# 4_motor.net
KiCad netlist of a schematic drawn in Altium Designer
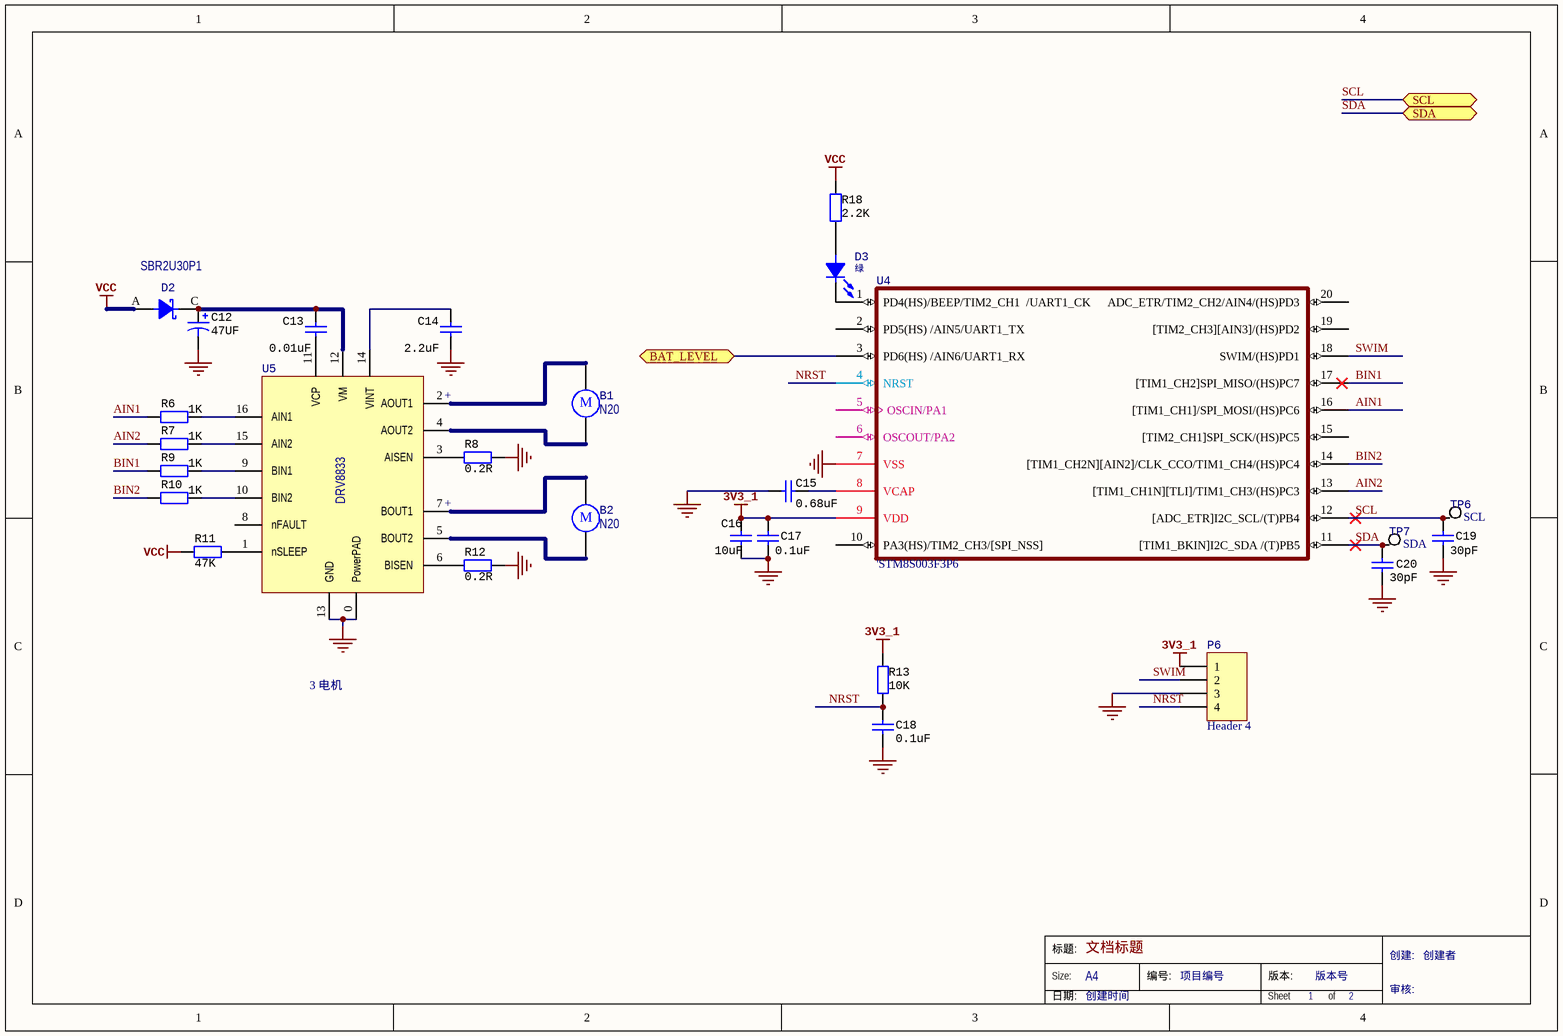
[diagram p0: 4.motor.SchDoc]

(export (version "E")
  (design (tool "Eeschema 10.0.6"))
  (components
    (comp (ref "B1")
      (value "N20")
      (footprint "2PIN/2.54MM座子")
      (description "Motor, General Kind")
      (fields (field (name "PUBLISHER") "Altium Limited"))
      (libsource (lib "Miscellaneous Devices") (part "Motor"))
    )
    (comp (ref "B2")
      (value "N20")
      (footprint "2PIN/2.54MM座子")
      (description "Motor, General Kind")
      (fields (field (name "PUBLISHER") "Altium Limited"))
      (libsource (lib "Miscellaneous Devices") (part "Motor"))
    )
    (comp (ref "C12")
      (value "47UF")
      (footprint "0805")
      (description "CAP ALUM 22UF 10V 20% SMD")
      (fields
        (field (name "PARTNUMBER") "EEE-1AA220WR")
        (field (name "MANUFACTURER") "Panasonic - ECG")
        (field (name "PUBLISHER") "National Semiconductor")
      )
      (libsource (lib "03.常用器件") (part "CAP3_pol"))
    )
    (comp (ref "C13")
      (value "0.01uF")
      (footprint "0402")
      (description "CAP, CERM, 0.01uF, 100V, +/-5%, X7R, 0603")
      (fields (field (name "PARTNUMBER") "06031C103JAT2A") (field (name "MANUFACTURER") "AVX"))
      (libsource (lib "03.常用器件") (part "CAP1_npol"))
    )
    (comp (ref "C14")
      (value "2.2uF")
      (footprint "0402")
      (description "CAP, CERM, 0.01uF, 100V, +/-5%, X7R, 0603")
      (fields (field (name "PARTNUMBER") "06031C103JAT2A") (field (name "MANUFACTURER") "AVX"))
      (libsource (lib "03.常用器件") (part "CAP1_npol"))
    )
    (comp (ref "C15")
      (value "0.68uF")
      (footprint "0402")
      (description "CAP, CERM, 0.01uF, 100V, +/-5%, X7R, 0603")
      (fields (field (name "PARTNUMBER") "06031C103JAT2A") (field (name "MANUFACTURER") "AVX"))
      (libsource (lib "03.常用器件") (part "CAP1_npol"))
    )
    (comp (ref "C16")
      (value "10uF")
      (footprint "0603")
      (description "CAP, CERM, 0.01uF, 100V, +/-5%, X7R, 0603")
      (fields (field (name "PARTNUMBER") "06031C103JAT2A") (field (name "MANUFACTURER") "AVX"))
      (libsource (lib "03.常用器件") (part "CAP1_npol"))
    )
    (comp (ref "C17")
      (value "0.1uF")
      (footprint "0402")
      (description "CAP, CERM, 0.01uF, 100V, +/-5%, X7R, 0603")
      (fields (field (name "PARTNUMBER") "06031C103JAT2A") (field (name "MANUFACTURER") "AVX"))
      (libsource (lib "03.常用器件") (part "CAP1_npol"))
    )
    (comp (ref "C18")
      (value "0.1uF")
      (footprint "0402")
      (description "CAP, CERM, 0.01uF, 100V, +/-5%, X7R, 0603")
      (fields (field (name "PARTNUMBER") "06031C103JAT2A") (field (name "MANUFACTURER") "AVX"))
      (libsource (lib "03.常用器件") (part "CAP1_npol"))
    )
    (comp (ref "C19")
      (value "30pF")
      (footprint "0402")
      (description "CAP, CERM, 0.01uF, 100V, +/-5%, X7R, 0603")
      (fields (field (name "PARTNUMBER") "06031C103JAT2A") (field (name "MANUFACTURER") "AVX"))
      (libsource (lib "03.常用器件") (part "CAP1_npol"))
    )
    (comp (ref "C20")
      (value "30pF")
      (footprint "0402")
      (description "CAP, CERM, 0.01uF, 100V, +/-5%, X7R, 0603")
      (fields (field (name "PARTNUMBER") "06031C103JAT2A") (field (name "MANUFACTURER") "AVX"))
      (libsource (lib "03.常用器件") (part "CAP1_npol"))
    )
    (comp (ref "D2")
      (value "SBR2U30P1")
      (footprint "POWERDI123")
      (fields (field (name "PARTNUMBER") "?") (field (name "PUBLISHER") "Altium Limited"))
      (libsource (lib "03.常用器件") (part "Diode_Schottky"))
    )
    (comp (ref "D3")
      (value "绿")
      (footprint "0603LED")
      (fields (field (name "MANUFACTURER") "?"))
      (libsource (lib "03.常用器件") (part "LED1"))
    )
    (comp (ref "P6")
      (value "Header 4")
      (footprint "排针2.54MM/4PIN")
      (description "Header, 4-Pin")
      (fields (field (name "PUBLISHER") "Altium Limited"))
      (libsource (lib "Miscellaneous Connectors") (part "Header 4"))
    )
    (comp (ref "R6")
      (value "1K")
      (footprint "0402")
      (description "RES, 1.0k ohm, 5%, 0.1W, 0603")
      (fields
        (field (name "PARTNUMBER") "RC0603JR-071KL")
        (field (name "MANUFACTURER") "Yageo America")
        (field (name "PUBLISHER") "Texas Instruments")
      )
      (libsource (lib "03.常用器件") (part "RES1"))
    )
    (comp (ref "R7")
      (value "1K")
      (footprint "0402")
      (description "RES, 1.0k ohm, 5%, 0.1W, 0603")
      (fields
        (field (name "PARTNUMBER") "RC0603JR-071KL")
        (field (name "MANUFACTURER") "Yageo America")
        (field (name "PUBLISHER") "Texas Instruments")
      )
      (libsource (lib "03.常用器件") (part "RES1"))
    )
    (comp (ref "R8")
      (value "0.2R")
      (footprint "0603")
      (description "RES, 1.0k ohm, 5%, 0.1W, 0603")
      (fields
        (field (name "PARTNUMBER") "RC0603JR-071KL")
        (field (name "MANUFACTURER") "Yageo America")
        (field (name "PUBLISHER") "Texas Instruments")
      )
      (libsource (lib "03.常用器件") (part "RES1"))
    )
    (comp (ref "R9")
      (value "1K")
      (footprint "0402")
      (description "RES, 1.0k ohm, 5%, 0.1W, 0603")
      (fields
        (field (name "PARTNUMBER") "RC0603JR-071KL")
        (field (name "MANUFACTURER") "Yageo America")
        (field (name "PUBLISHER") "Texas Instruments")
      )
      (libsource (lib "03.常用器件") (part "RES1"))
    )
    (comp (ref "R10")
      (value "1K")
      (footprint "0402")
      (description "RES, 1.0k ohm, 5%, 0.1W, 0603")
      (fields
        (field (name "PARTNUMBER") "RC0603JR-071KL")
        (field (name "MANUFACTURER") "Yageo America")
        (field (name "PUBLISHER") "Texas Instruments")
      )
      (libsource (lib "03.常用器件") (part "RES1"))
    )
    (comp (ref "R11")
      (value "47K")
      (footprint "0402")
      (description "RES, 1.0k ohm, 5%, 0.1W, 0603")
      (fields
        (field (name "PARTNUMBER") "RC0603JR-071KL")
        (field (name "MANUFACTURER") "Yageo America")
        (field (name "PUBLISHER") "Texas Instruments")
      )
      (libsource (lib "03.常用器件") (part "RES1"))
    )
    (comp (ref "R12")
      (value "0.2R")
      (footprint "0603")
      (description "RES, 1.0k ohm, 5%, 0.1W, 0603")
      (fields
        (field (name "PARTNUMBER") "RC0603JR-071KL")
        (field (name "MANUFACTURER") "Yageo America")
        (field (name "PUBLISHER") "Texas Instruments")
      )
      (libsource (lib "03.常用器件") (part "RES1"))
    )
    (comp (ref "R13")
      (value "10K")
      (footprint "0402")
      (description "RES, 1.0k ohm, 5%, 0.1W, 0603")
      (fields
        (field (name "PARTNUMBER") "RC0603JR-071KL")
        (field (name "MANUFACTURER") "Yageo America")
        (field (name "PUBLISHER") "Texas Instruments")
      )
      (libsource (lib "") (part "RES1_1"))
    )
    (comp (ref "R18")
      (value "2.2K")
      (footprint "0402")
      (description "RES, 1.0k ohm, 5%, 0.1W, 0603")
      (fields
        (field (name "PARTNUMBER") "RC0603JR-071KL")
        (field (name "MANUFACTURER") "Yageo America")
        (field (name "PUBLISHER") "Texas Instruments")
      )
      (libsource (lib "") (part "RES1_1"))
    )
    (comp (ref "TP6")
      (value "SCL")
      (footprint "测试点")
      (description "Test Point")
      (libsource (lib "my_Schlib") (part "TP"))
    )
    (comp (ref "TP7")
      (value "SDA")
      (footprint "测试点")
      (description "Test Point")
      (libsource (lib "my_Schlib") (part "TP"))
    )
    (comp (ref "U4")
      (value "'STM8S003F3P6")
      (footprint "UFQFPN20")
      (description "ST 8-bit  Microcontroller")
      (libsource (lib "Microcontroller Unit") (part "STM8S103F2P6"))
    )
    (comp (ref "U5")
      (value "DRV8833")
      (footprint "HTSSOP -16(PWP)")
      (description "DUAL H-BRIDGE MOTOR DRIVER")
      (libsource (lib "DRV8833") (part "DRV8833PWP"))
    )
  )
  (nets
    (net (code "1") (name "/AIN1") (class "Default")
      (node (ref "R6") (pin "1") (pinfunction "1_1") (pintype "passive"))
      (node (ref "U4") (pin "16") (pinfunction "[TIM1_CH1]/SPI_MOSI/(HS)PC6_16") (pintype "bidirectional"))
    )
    (net (code "2") (name "/AIN2") (class "Default")
      (node (ref "R7") (pin "1") (pinfunction "1_1") (pintype "passive"))
      (node (ref "U4") (pin "13") (pinfunction "[TIM1_CH1N][TLI]/TIM1_CH3/(HS)PC3_13") (pintype "bidirectional"))
    )
    (net (code "3") (name "/BAT_LEVEL") (class "Default")
      (node (ref "U4") (pin "3") (pinfunction "PD6(HS)_/AIN6/UART1_RX_3") (pintype "bidirectional"))
    )
    (net (code "4") (name "/BIN1") (class "Default")
      (node (ref "R9") (pin "1") (pinfunction "1_1") (pintype "passive"))
      (node (ref "U4") (pin "17") (pinfunction "[TIM1_CH2]SPI_MISO/(HS)PC7_17") (pintype "bidirectional"))
    )
    (net (code "5") (name "/BIN2") (class "Default")
      (node (ref "R10") (pin "1") (pinfunction "1_1") (pintype "passive"))
      (node (ref "U4") (pin "14") (pinfunction "[TIM1_CH2N][AIN2]/CLK_CCO/TIM1_CH4/(HS)PC4_14") (pintype "bidirectional"))
    )
    (net (code "6") (name "/NRST") (class "Default")
      (node (ref "C18") (pin "2") (pinfunction "2_2") (pintype "passive"))
      (node (ref "P6") (pin "4") (pinfunction "4_4") (pintype "passive"))
      (node (ref "R13") (pin "2") (pinfunction "2_2") (pintype "passive"))
      (node (ref "U4") (pin "4") (pinfunction "NRST_4") (pintype "bidirectional"))
    )
    (net (code "9") (name "/SWIM") (class "Default")
      (node (ref "P6") (pin "2") (pinfunction "2_2") (pintype "passive"))
      (node (ref "U4") (pin "18") (pinfunction "SWIM/(HS)PD1_18") (pintype "bidirectional"))
    )
    (net (code "10") (name "3V3_1") (class "Default")
      (node (ref "C16") (pin "1") (pinfunction "1_1") (pintype "passive"))
      (node (ref "C17") (pin "2") (pinfunction "2_2") (pintype "passive"))
      (node (ref "P6") (pin "1") (pinfunction "1_1") (pintype "passive"))
      (node (ref "R13") (pin "1") (pinfunction "1_1") (pintype "passive"))
      (node (ref "U4") (pin "9") (pinfunction "VDD_9") (pintype "power_in"))
    )
    (net (code "11") (name "<NO NET>") (class "Default")
      (node (ref "C12") (pin "2") (pinfunction "-_2") (pintype "passive"))
      (node (ref "C14") (pin "1") (pinfunction "1_1") (pintype "passive"))
      (node (ref "C15") (pin "2") (pinfunction "2_2") (pintype "passive"))
      (node (ref "C16") (pin "2") (pinfunction "2_2") (pintype "passive"))
      (node (ref "C17") (pin "1") (pinfunction "1_1") (pintype "passive"))
      (node (ref "C18") (pin "1") (pinfunction "1_1") (pintype "passive"))
      (node (ref "C19") (pin "1") (pinfunction "1_1") (pintype "passive"))
      (node (ref "C20") (pin "1") (pinfunction "1_1") (pintype "passive"))
      (node (ref "P6") (pin "3") (pinfunction "3_3") (pintype "passive"))
      (node (ref "R12") (pin "2") (pinfunction "2_2") (pintype "passive"))
      (node (ref "R8") (pin "2") (pinfunction "2_2") (pintype "passive"))
      (node (ref "U4") (pin "7") (pinfunction "VSS_7") (pintype "power_in"))
      (node (ref "U5") (pin "0") (pinfunction "PowerPAD_0") (pintype "passive"))
      (node (ref "U5") (pin "13") (pinfunction "GND_13") (pintype "passive"))
    )
    (net (code "12") (name "Net-(C12-+)") (class "Default")
      (node (ref "C12") (pin "1") (pinfunction "+_1") (pintype "passive"))
      (node (ref "C13") (pin "2") (pinfunction "2_2") (pintype "passive"))
      (node (ref "D2") (pin "C") (pinfunction "CATHODE_C") (pintype "passive"))
      (node (ref "U5") (pin "12") (pinfunction "VM_12") (pintype "passive"))
    )
    (net (code "13") (name "Net-(D3-ANODE)") (class "Default")
      (node (ref "D3") (pin "A") (pinfunction "ANODE_A") (pintype "passive"))
      (node (ref "R18") (pin "2") (pinfunction "2_2") (pintype "passive"))
    )
    (net (code "14") (name "Net-(D3-CATHODE)") (class "Default")
      (node (ref "D3") (pin "C") (pinfunction "CATHODE_C") (pintype "passive"))
      (node (ref "U4") (pin "1") (pinfunction "PD4(HS)/BEEP/TIM2_CH1__/UART1_CK_1") (pintype "bidirectional"))
    )
    (net (code "15") (name "Net-(U4-VCAP)") (class "Default")
      (node (ref "C15") (pin "1") (pinfunction "1_1") (pintype "passive"))
      (node (ref "U4") (pin "8") (pinfunction "VCAP_8") (pintype "power_in"))
    )
    (net (code "16") (name "Net-(U4-[ADC_ETR]I2C_SCL{slash}(T)PB4)") (class "Default")
      (node (ref "C19") (pin "2") (pinfunction "2_2") (pintype "passive"))
      (node (ref "TP6") (pin "1") (pinfunction "1_1") (pintype "passive"))
      (node (ref "U4") (pin "12") (pinfunction "[ADC_ETR]I2C_SCL/(T)PB4_12") (pintype "bidirectional"))
    )
    (net (code "17") (name "Net-(U4-[TIM1_BKIN]I2C_SDA_{slash}(T)PB5)") (class "Default")
      (node (ref "C20") (pin "2") (pinfunction "2_2") (pintype "passive"))
      (node (ref "TP7") (pin "1") (pinfunction "1_1") (pintype "passive"))
      (node (ref "U4") (pin "11") (pinfunction "[TIM1_BKIN]I2C_SDA_/(T)PB5_11") (pintype "bidirectional"))
    )
    (net (code "18") (name "Net-(U5-AIN1)") (class "Default")
      (node (ref "R6") (pin "2") (pinfunction "2_2") (pintype "passive"))
      (node (ref "U5") (pin "16") (pinfunction "AIN1_16") (pintype "passive"))
    )
    (net (code "19") (name "Net-(U5-AIN2)") (class "Default")
      (node (ref "R7") (pin "2") (pinfunction "2_2") (pintype "passive"))
      (node (ref "U5") (pin "15") (pinfunction "AIN2_15") (pintype "passive"))
    )
    (net (code "20") (name "Net-(U5-AISEN)") (class "Default")
      (node (ref "R8") (pin "1") (pinfunction "1_1") (pintype "passive"))
      (node (ref "U5") (pin "3") (pinfunction "AISEN_3") (pintype "passive"))
    )
    (net (code "21") (name "Net-(U5-AOUT1)") (class "Default")
      (node (ref "B1") (pin "1") (pinfunction "1_1") (pintype "passive"))
      (node (ref "U5") (pin "2") (pinfunction "AOUT1_2") (pintype "passive"))
    )
    (net (code "22") (name "Net-(U5-AOUT2)") (class "Default")
      (node (ref "B1") (pin "2") (pinfunction "2_2") (pintype "passive"))
      (node (ref "U5") (pin "4") (pinfunction "AOUT2_4") (pintype "passive"))
    )
    (net (code "23") (name "Net-(U5-BIN1)") (class "Default")
      (node (ref "R9") (pin "2") (pinfunction "2_2") (pintype "passive"))
      (node (ref "U5") (pin "9") (pinfunction "BIN1_9") (pintype "passive"))
    )
    (net (code "24") (name "Net-(U5-BIN2)") (class "Default")
      (node (ref "R10") (pin "2") (pinfunction "2_2") (pintype "passive"))
      (node (ref "U5") (pin "10") (pinfunction "BIN2_10") (pintype "passive"))
    )
    (net (code "25") (name "Net-(U5-BISEN)") (class "Default")
      (node (ref "R12") (pin "1") (pinfunction "1_1") (pintype "passive"))
      (node (ref "U5") (pin "6") (pinfunction "BISEN_6") (pintype "passive"))
    )
    (net (code "26") (name "Net-(U5-BOUT1)") (class "Default")
      (node (ref "B2") (pin "1") (pinfunction "1_1") (pintype "passive"))
      (node (ref "U5") (pin "7") (pinfunction "BOUT1_7") (pintype "passive"))
    )
    (net (code "27") (name "Net-(U5-BOUT2)") (class "Default")
      (node (ref "B2") (pin "2") (pinfunction "2_2") (pintype "passive"))
      (node (ref "U5") (pin "5") (pinfunction "BOUT2_5") (pintype "passive"))
    )
    (net (code "28") (name "Net-(U5-VCP)") (class "Default")
      (node (ref "C13") (pin "1") (pinfunction "1_1") (pintype "passive"))
      (node (ref "U5") (pin "11") (pinfunction "VCP_11") (pintype "passive"))
    )
    (net (code "29") (name "Net-(U5-VINT)") (class "Default")
      (node (ref "C14") (pin "2") (pinfunction "2_2") (pintype "passive"))
      (node (ref "U5") (pin "14") (pinfunction "VINT_14") (pintype "passive"))
    )
    (net (code "30") (name "Net-(U5-nSLEEP)") (class "Default")
      (node (ref "R11") (pin "2") (pinfunction "2_2") (pintype "passive"))
      (node (ref "U5") (pin "1") (pinfunction "nSLEEP_1") (pintype "passive"))
    )
    (net (code "31") (name "VCC") (class "Default")
      (node (ref "D2") (pin "A") (pinfunction "ANODE_A") (pintype "passive"))
      (node (ref "R11") (pin "1") (pinfunction "1_1") (pintype "passive"))
      (node (ref "R18") (pin "1") (pinfunction "1_1") (pintype "passive"))
    )
    (net (code "32") (name "unconnected-(U4-ADC_ETR{slash}TIM2_CH2{slash}AIN4{slash}(HS)PD3-Pad20)") (class "Default")
      (node (ref "U4") (pin "20") (pinfunction "ADC_ETR/TIM2_CH2/AIN4/(HS)PD3_20") (pintype "bidirectional"))
    )
    (net (code "33") (name "unconnected-(U4-OSCIN{slash}PA1-Pad5)") (class "Default")
      (node (ref "U4") (pin "5") (pinfunction "OSCIN/PA1_5") (pintype "bidirectional"))
    )
    (net (code "34") (name "unconnected-(U4-OSCOUT{slash}PA2-Pad6)") (class "Default")
      (node (ref "U4") (pin "6") (pinfunction "OSCOUT/PA2_6") (pintype "bidirectional"))
    )
    (net (code "35") (name "unconnected-(U4-PA3(HS){slash}TIM2_CH3{slash}[SPI_NSS]-Pad10)") (class "Default")
      (node (ref "U4") (pin "10") (pinfunction "PA3(HS)/TIM2_CH3/[SPI_NSS]_10") (pintype "bidirectional"))
    )
    (net (code "36") (name "unconnected-(U4-PD5(HS)_{slash}AIN5{slash}UART1_TX-Pad2)") (class "Default")
      (node (ref "U4") (pin "2") (pinfunction "PD5(HS)_/AIN5/UART1_TX_2") (pintype "bidirectional"))
    )
    (net (code "37") (name "unconnected-(U4-[TIM2_CH1]SPI_SCK{slash}(HS)PC5-Pad15)") (class "Default")
      (node (ref "U4") (pin "15") (pinfunction "[TIM2_CH1]SPI_SCK/(HS)PC5_15") (pintype "bidirectional"))
    )
    (net (code "38") (name "unconnected-(U4-[TIM2_CH3][AIN3]{slash}(HS)PD2-Pad19)") (class "Default")
      (node (ref "U4") (pin "19") (pinfunction "[TIM2_CH3][AIN3]/(HS)PD2_19") (pintype "bidirectional"))
    )
    (net (code "39") (name "unconnected-(U5-nFAULT-Pad8)") (class "Default")
      (node (ref "U5") (pin "8") (pinfunction "nFAULT_8") (pintype "passive"))
    )
  )
)
